# o.net
KiCad netlist of a schematic drawn in EAGLE
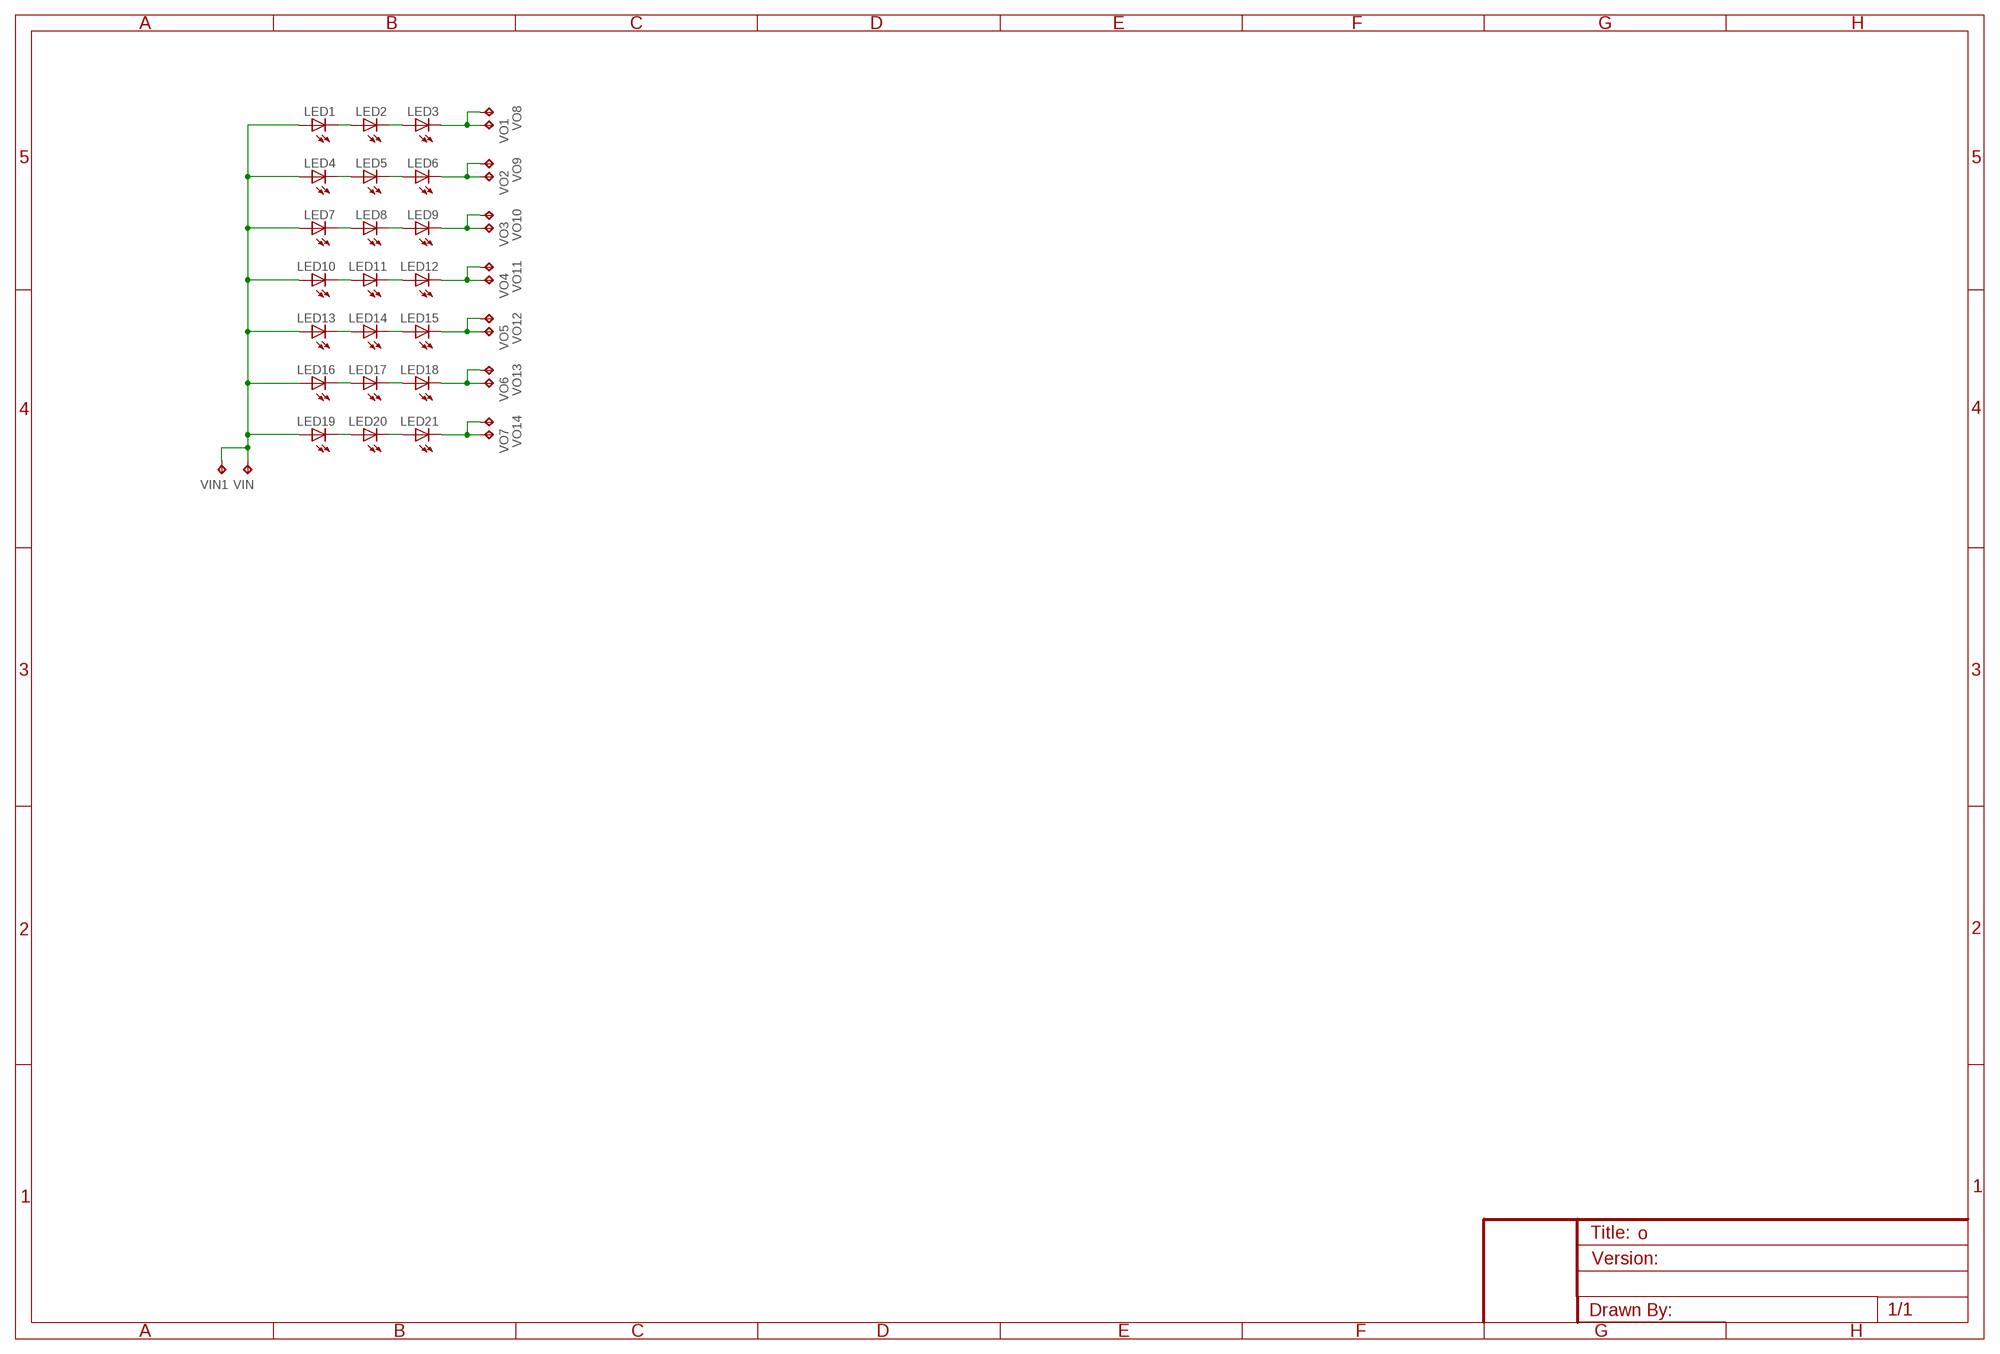
[diagram p0: schematic, sheet 1]

(export (version "E")
  (design (tool "Eeschema 10.0.6"))
  (components
    (comp (ref "LED1")
      (value "LED0805")
      (footprint "eagle-import:LED_0805")
      (libsource (lib "eagle-import") (part "LED0805"))
    )
    (comp (ref "LED2")
      (value "LED0805")
      (footprint "eagle-import:LED_0805")
      (libsource (lib "eagle-import") (part "LED0805"))
    )
    (comp (ref "LED3")
      (value "LED0805")
      (footprint "eagle-import:LED_0805")
      (libsource (lib "eagle-import") (part "LED0805"))
    )
    (comp (ref "LED4")
      (value "LED0805")
      (footprint "eagle-import:LED_0805")
      (libsource (lib "eagle-import") (part "LED0805"))
    )
    (comp (ref "LED5")
      (value "LED0805")
      (footprint "eagle-import:LED_0805")
      (libsource (lib "eagle-import") (part "LED0805"))
    )
    (comp (ref "LED6")
      (value "LED0805")
      (footprint "eagle-import:LED_0805")
      (libsource (lib "eagle-import") (part "LED0805"))
    )
    (comp (ref "LED7")
      (value "LED0805")
      (footprint "eagle-import:LED_0805")
      (libsource (lib "eagle-import") (part "LED0805"))
    )
    (comp (ref "LED8")
      (value "LED0805")
      (footprint "eagle-import:LED_0805")
      (libsource (lib "eagle-import") (part "LED0805"))
    )
    (comp (ref "LED9")
      (value "LED0805")
      (footprint "eagle-import:LED_0805")
      (libsource (lib "eagle-import") (part "LED0805"))
    )
    (comp (ref "LED10")
      (value "LED0805")
      (footprint "eagle-import:LED_0805")
      (libsource (lib "eagle-import") (part "LED0805"))
    )
    (comp (ref "LED11")
      (value "LED0805")
      (footprint "eagle-import:LED_0805")
      (libsource (lib "eagle-import") (part "LED0805"))
    )
    (comp (ref "LED12")
      (value "LED0805")
      (footprint "eagle-import:LED_0805")
      (libsource (lib "eagle-import") (part "LED0805"))
    )
    (comp (ref "LED13")
      (value "LED0805")
      (footprint "eagle-import:LED_0805")
      (libsource (lib "eagle-import") (part "LED0805"))
    )
    (comp (ref "LED14")
      (value "LED0805")
      (footprint "eagle-import:LED_0805")
      (libsource (lib "eagle-import") (part "LED0805"))
    )
    (comp (ref "LED15")
      (value "LED0805")
      (footprint "eagle-import:LED_0805")
      (libsource (lib "eagle-import") (part "LED0805"))
    )
    (comp (ref "LED16")
      (value "LED0805")
      (footprint "eagle-import:LED_0805")
      (libsource (lib "eagle-import") (part "LED0805"))
    )
    (comp (ref "LED17")
      (value "LED0805")
      (footprint "eagle-import:LED_0805")
      (libsource (lib "eagle-import") (part "LED0805"))
    )
    (comp (ref "LED18")
      (value "LED0805")
      (footprint "eagle-import:LED_0805")
      (libsource (lib "eagle-import") (part "LED0805"))
    )
    (comp (ref "LED19")
      (value "LED0805")
      (footprint "eagle-import:LED_0805")
      (libsource (lib "eagle-import") (part "LED0805"))
    )
    (comp (ref "LED20")
      (value "LED0805")
      (footprint "eagle-import:LED_0805")
      (libsource (lib "eagle-import") (part "LED0805"))
    )
    (comp (ref "LED21")
      (value "LED0805")
      (footprint "eagle-import:LED_0805")
      (libsource (lib "eagle-import") (part "LED0805"))
    )
    (comp (ref "VIN")
      (value "TEST_POINTPAD1-20")
      (footprint "eagle-import:P1-20")
      (libsource (lib "eagle-import") (part "TEST_POINTPAD1-20"))
    )
    (comp (ref "VIN1")
      (value "TEST_POINTPAD1-20")
      (footprint "eagle-import:P1-20")
      (libsource (lib "eagle-import") (part "TEST_POINTPAD1-20"))
    )
    (comp (ref "VO1")
      (value "TEST_POINTPAD1-20")
      (footprint "eagle-import:P1-20")
      (libsource (lib "eagle-import") (part "TEST_POINTPAD1-20"))
    )
    (comp (ref "VO2")
      (value "TEST_POINTPAD1-20")
      (footprint "eagle-import:P1-20")
      (libsource (lib "eagle-import") (part "TEST_POINTPAD1-20"))
    )
    (comp (ref "VO3")
      (value "TEST_POINTPAD1-20")
      (footprint "eagle-import:P1-20")
      (libsource (lib "eagle-import") (part "TEST_POINTPAD1-20"))
    )
    (comp (ref "VO4")
      (value "TEST_POINTPAD1-20")
      (footprint "eagle-import:P1-20")
      (libsource (lib "eagle-import") (part "TEST_POINTPAD1-20"))
    )
    (comp (ref "VO5")
      (value "TEST_POINTPAD1-20")
      (footprint "eagle-import:P1-20")
      (libsource (lib "eagle-import") (part "TEST_POINTPAD1-20"))
    )
    (comp (ref "VO6")
      (value "TEST_POINTPAD1-20")
      (footprint "eagle-import:P1-20")
      (libsource (lib "eagle-import") (part "TEST_POINTPAD1-20"))
    )
    (comp (ref "VO7")
      (value "TEST_POINTPAD1-20")
      (footprint "eagle-import:P1-20")
      (libsource (lib "eagle-import") (part "TEST_POINTPAD1-20"))
    )
    (comp (ref "VO8")
      (value "TEST_POINTPAD1-20")
      (footprint "eagle-import:P1-20")
      (libsource (lib "eagle-import") (part "TEST_POINTPAD1-20"))
    )
    (comp (ref "VO9")
      (value "TEST_POINTPAD1-20")
      (footprint "eagle-import:P1-20")
      (libsource (lib "eagle-import") (part "TEST_POINTPAD1-20"))
    )
    (comp (ref "VO10")
      (value "TEST_POINTPAD1-20")
      (footprint "eagle-import:P1-20")
      (libsource (lib "eagle-import") (part "TEST_POINTPAD1-20"))
    )
    (comp (ref "VO11")
      (value "TEST_POINTPAD1-20")
      (footprint "eagle-import:P1-20")
      (libsource (lib "eagle-import") (part "TEST_POINTPAD1-20"))
    )
    (comp (ref "VO12")
      (value "TEST_POINTPAD1-20")
      (footprint "eagle-import:P1-20")
      (libsource (lib "eagle-import") (part "TEST_POINTPAD1-20"))
    )
    (comp (ref "VO13")
      (value "TEST_POINTPAD1-20")
      (footprint "eagle-import:P1-20")
      (libsource (lib "eagle-import") (part "TEST_POINTPAD1-20"))
    )
    (comp (ref "VO14")
      (value "TEST_POINTPAD1-20")
      (footprint "eagle-import:P1-20")
      (libsource (lib "eagle-import") (part "TEST_POINTPAD1-20"))
    )
  )
  (nets
    (net (code "1") (name "Net-(LED1-PadA)") (class "Default")
      (node (ref "LED1") (pin "A") (pinfunction "A_A") (pintype "passive"))
      (node (ref "LED10") (pin "A") (pinfunction "A_A") (pintype "passive"))
      (node (ref "LED13") (pin "A") (pinfunction "A_A") (pintype "passive"))
      (node (ref "LED16") (pin "A") (pinfunction "A_A") (pintype "passive"))
      (node (ref "LED19") (pin "A") (pinfunction "A_A") (pintype "passive"))
      (node (ref "LED4") (pin "A") (pinfunction "A_A") (pintype "passive"))
      (node (ref "LED7") (pin "A") (pinfunction "A_A") (pintype "passive"))
      (node (ref "VIN") (pin "TP") (pinfunction "TP_TP") (pintype "input"))
      (node (ref "VIN1") (pin "TP") (pinfunction "TP_TP") (pintype "input"))
    )
    (net (code "2") (name "Net-(LED1-PadC)") (class "Default")
      (node (ref "LED1") (pin "C") (pinfunction "C_C") (pintype "passive"))
      (node (ref "LED2") (pin "A") (pinfunction "A_A") (pintype "passive"))
    )
    (net (code "3") (name "Net-(LED2-PadC)") (class "Default")
      (node (ref "LED2") (pin "C") (pinfunction "C_C") (pintype "passive"))
      (node (ref "LED3") (pin "A") (pinfunction "A_A") (pintype "passive"))
    )
    (net (code "4") (name "Net-(LED3-PadC)") (class "Default")
      (node (ref "LED3") (pin "C") (pinfunction "C_C") (pintype "passive"))
      (node (ref "VO1") (pin "TP") (pinfunction "TP_TP") (pintype "input"))
      (node (ref "VO8") (pin "TP") (pinfunction "TP_TP") (pintype "input"))
    )
    (net (code "5") (name "Net-(LED4-PadC)") (class "Default")
      (node (ref "LED4") (pin "C") (pinfunction "C_C") (pintype "passive"))
      (node (ref "LED5") (pin "A") (pinfunction "A_A") (pintype "passive"))
    )
    (net (code "6") (name "Net-(LED5-PadC)") (class "Default")
      (node (ref "LED5") (pin "C") (pinfunction "C_C") (pintype "passive"))
      (node (ref "LED6") (pin "A") (pinfunction "A_A") (pintype "passive"))
    )
    (net (code "7") (name "Net-(LED6-PadC)") (class "Default")
      (node (ref "LED6") (pin "C") (pinfunction "C_C") (pintype "passive"))
      (node (ref "VO2") (pin "TP") (pinfunction "TP_TP") (pintype "input"))
      (node (ref "VO9") (pin "TP") (pinfunction "TP_TP") (pintype "input"))
    )
    (net (code "8") (name "Net-(LED7-PadC)") (class "Default")
      (node (ref "LED7") (pin "C") (pinfunction "C_C") (pintype "passive"))
      (node (ref "LED8") (pin "A") (pinfunction "A_A") (pintype "passive"))
    )
    (net (code "9") (name "Net-(LED8-PadC)") (class "Default")
      (node (ref "LED8") (pin "C") (pinfunction "C_C") (pintype "passive"))
      (node (ref "LED9") (pin "A") (pinfunction "A_A") (pintype "passive"))
    )
    (net (code "10") (name "Net-(LED9-PadC)") (class "Default")
      (node (ref "LED9") (pin "C") (pinfunction "C_C") (pintype "passive"))
      (node (ref "VO10") (pin "TP") (pinfunction "TP_TP") (pintype "input"))
      (node (ref "VO3") (pin "TP") (pinfunction "TP_TP") (pintype "input"))
    )
    (net (code "11") (name "Net-(LED10-PadC)") (class "Default")
      (node (ref "LED10") (pin "C") (pinfunction "C_C") (pintype "passive"))
      (node (ref "LED11") (pin "A") (pinfunction "A_A") (pintype "passive"))
    )
    (net (code "12") (name "Net-(LED11-PadC)") (class "Default")
      (node (ref "LED11") (pin "C") (pinfunction "C_C") (pintype "passive"))
      (node (ref "LED12") (pin "A") (pinfunction "A_A") (pintype "passive"))
    )
    (net (code "13") (name "Net-(LED12-PadC)") (class "Default")
      (node (ref "LED12") (pin "C") (pinfunction "C_C") (pintype "passive"))
      (node (ref "VO11") (pin "TP") (pinfunction "TP_TP") (pintype "input"))
      (node (ref "VO4") (pin "TP") (pinfunction "TP_TP") (pintype "input"))
    )
    (net (code "14") (name "Net-(LED13-PadC)") (class "Default")
      (node (ref "LED13") (pin "C") (pinfunction "C_C") (pintype "passive"))
      (node (ref "LED14") (pin "A") (pinfunction "A_A") (pintype "passive"))
    )
    (net (code "15") (name "Net-(LED14-PadC)") (class "Default")
      (node (ref "LED14") (pin "C") (pinfunction "C_C") (pintype "passive"))
      (node (ref "LED15") (pin "A") (pinfunction "A_A") (pintype "passive"))
    )
    (net (code "16") (name "Net-(LED15-PadC)") (class "Default")
      (node (ref "LED15") (pin "C") (pinfunction "C_C") (pintype "passive"))
      (node (ref "VO12") (pin "TP") (pinfunction "TP_TP") (pintype "input"))
      (node (ref "VO5") (pin "TP") (pinfunction "TP_TP") (pintype "input"))
    )
    (net (code "17") (name "Net-(LED16-PadC)") (class "Default")
      (node (ref "LED16") (pin "C") (pinfunction "C_C") (pintype "passive"))
      (node (ref "LED17") (pin "A") (pinfunction "A_A") (pintype "passive"))
    )
    (net (code "18") (name "Net-(LED17-PadC)") (class "Default")
      (node (ref "LED17") (pin "C") (pinfunction "C_C") (pintype "passive"))
      (node (ref "LED18") (pin "A") (pinfunction "A_A") (pintype "passive"))
    )
    (net (code "19") (name "Net-(LED18-PadC)") (class "Default")
      (node (ref "LED18") (pin "C") (pinfunction "C_C") (pintype "passive"))
      (node (ref "VO13") (pin "TP") (pinfunction "TP_TP") (pintype "input"))
      (node (ref "VO6") (pin "TP") (pinfunction "TP_TP") (pintype "input"))
    )
    (net (code "20") (name "Net-(LED19-PadC)") (class "Default")
      (node (ref "LED19") (pin "C") (pinfunction "C_C") (pintype "passive"))
      (node (ref "LED20") (pin "A") (pinfunction "A_A") (pintype "passive"))
    )
    (net (code "21") (name "Net-(LED20-PadC)") (class "Default")
      (node (ref "LED20") (pin "C") (pinfunction "C_C") (pintype "passive"))
      (node (ref "LED21") (pin "A") (pinfunction "A_A") (pintype "passive"))
    )
    (net (code "22") (name "Net-(LED21-PadC)") (class "Default")
      (node (ref "LED21") (pin "C") (pinfunction "C_C") (pintype "passive"))
      (node (ref "VO14") (pin "TP") (pinfunction "TP_TP") (pintype "input"))
      (node (ref "VO7") (pin "TP") (pinfunction "TP_TP") (pintype "input"))
    )
  )
)
